# DM1092_uSD.net
KiCad netlist of a schematic drawn in Altium Designer
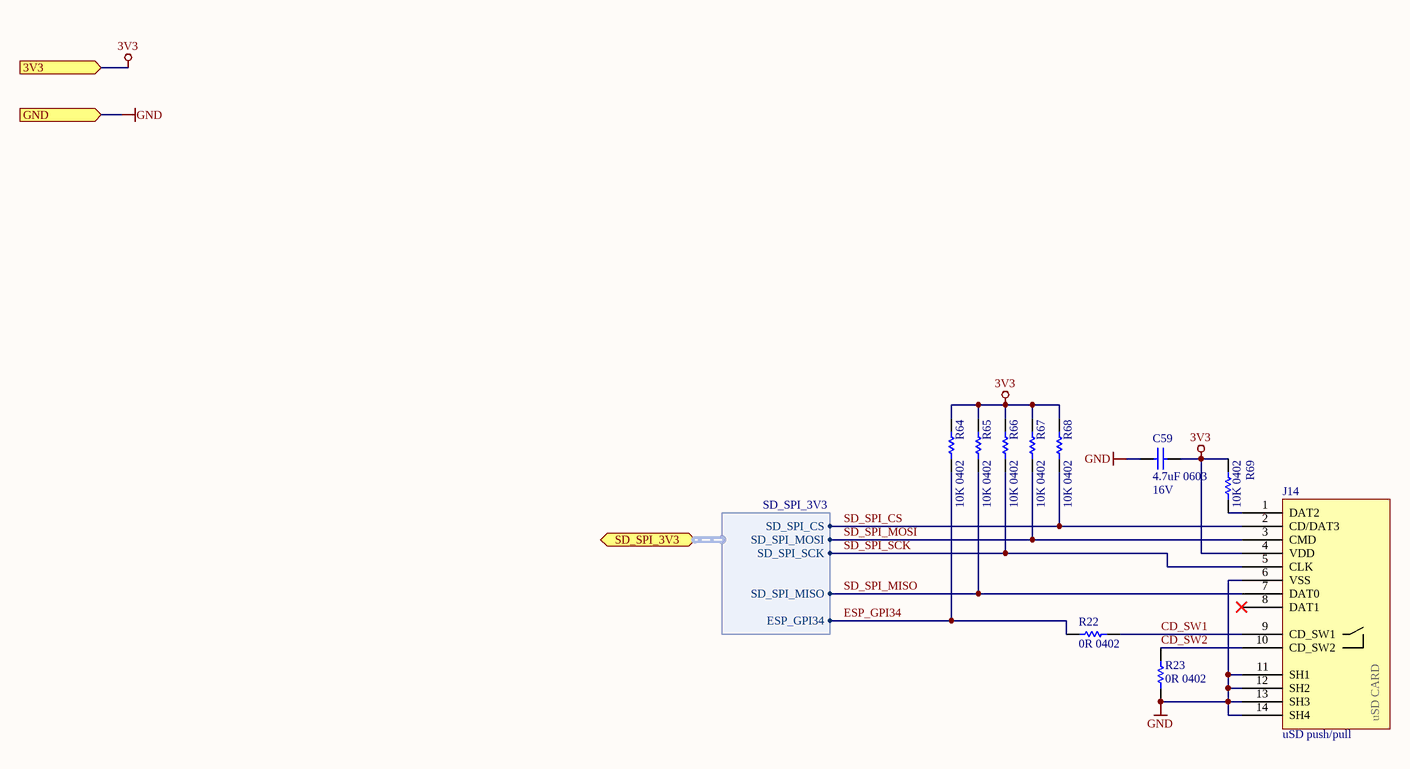
[diagram p0: DM1092_uSD.SchDoc]

(export (version "E")
  (design (tool "Eeschema 10.0.6"))
  (components
    (comp (ref "C59")
      (value "4.7uF 0603")
      (footprint "CAP_Altium_Vault_Generic:CAPC0603(1608)100_N")
      (description "CAP CER 4.7UF 16V X5R 0603 10%")
      (fields (field (name "TOLERANCE") "10%") (field (name "VOLTAGE RATING") "16V"))
      (libsource (lib "LuxonisMaster") (part "GRM188R61C475KAAJD"))
    )
    (comp (ref "J14")
      (value "uSD push/pull")
      (footprint "LuxonisMaster:104031-0811")
      (description "CONN MICRO SD CARD PUSH-PULL R/A")
      (libsource (lib "LuxonisMaster") (part "104031-0811"))
    )
    (comp (ref "R22")
      (value "0R 0402")
      (footprint "RES_Altium_Vault_Generic:RESC0402(1005)_N")
      (description "RES SMD 0 OHM JUMPER 1/16W 0402")
      (fields (field (name "TOLERANCE") "5%"))
      (libsource (lib "LuxonisMaster") (part "CRCW04020000Z0ED"))
    )
    (comp (ref "R23")
      (value "0R 0402")
      (footprint "RES_Altium_Vault_Generic:RESC0402(1005)_N")
      (description "RES SMD 0 OHM JUMPER 1/16W 0402")
      (fields (field (name "TOLERANCE") "5%"))
      (libsource (lib "LuxonisMaster") (part "CRCW04020000Z0ED"))
    )
    (comp (ref "R64")
      (value "10K 0402")
      (footprint "RES_Altium_Vault_Generic:RESC0402(1005)_N")
      (fields (field (name "TOLERANCE") "1%"))
      (libsource (lib "LuxonisMaster") (part "RC0402FR-1310KL"))
    )
    (comp (ref "R65")
      (value "10K 0402")
      (footprint "RES_Altium_Vault_Generic:RESC0402(1005)_N")
      (fields (field (name "TOLERANCE") "1%"))
      (libsource (lib "LuxonisMaster") (part "RC0402FR-1310KL"))
    )
    (comp (ref "R66")
      (value "10K 0402")
      (footprint "RES_Altium_Vault_Generic:RESC0402(1005)_N")
      (fields (field (name "TOLERANCE") "1%"))
      (libsource (lib "LuxonisMaster") (part "RC0402FR-1310KL"))
    )
    (comp (ref "R67")
      (value "10K 0402")
      (footprint "RES_Altium_Vault_Generic:RESC0402(1005)_N")
      (fields (field (name "TOLERANCE") "1%"))
      (libsource (lib "LuxonisMaster") (part "RC0402FR-1310KL"))
    )
    (comp (ref "R68")
      (value "10K 0402")
      (footprint "RES_Altium_Vault_Generic:RESC0402(1005)_N")
      (fields (field (name "TOLERANCE") "1%"))
      (libsource (lib "LuxonisMaster") (part "RC0402FR-1310KL"))
    )
    (comp (ref "R69")
      (value "10K 0402")
      (footprint "RES_Altium_Vault_Generic:RESC0402(1005)_N")
      (fields (field (name "TOLERANCE") "1%"))
      (libsource (lib "LuxonisMaster") (part "RC0402FR-1310KL"))
    )
  )
  (nets
    (net (code "2") (name "/CD_SW1") (class "Default")
      (node (ref "J14") (pin "9") (pinfunction "CD_SW1_9") (pintype "passive"))
      (node (ref "R22") (pin "1") (pinfunction "1_1") (pintype "passive"))
    )
    (net (code "3") (name "/CD_SW2") (class "Default")
      (node (ref "J14") (pin "10") (pinfunction "CD_SW2_10") (pintype "passive"))
      (node (ref "R23") (pin "2") (pinfunction "2_2") (pintype "passive"))
    )
    (net (code "4") (name "/ESP_GPI34") (class "Default")
      (node (ref "R22") (pin "2") (pinfunction "2_2") (pintype "passive"))
      (node (ref "R64") (pin "1") (pinfunction "1_1") (pintype "passive"))
    )
    (net (code "5") (name "/SD_SPI_CS") (class "Default")
      (node (ref "J14") (pin "2") (pinfunction "CD/DAT3_2") (pintype "passive"))
      (node (ref "R68") (pin "1") (pinfunction "1_1") (pintype "passive"))
    )
    (net (code "6") (name "/SD_SPI_MISO") (class "Default")
      (node (ref "J14") (pin "7") (pinfunction "DAT0_7") (pintype "passive"))
      (node (ref "R65") (pin "1") (pinfunction "1_1") (pintype "passive"))
    )
    (net (code "7") (name "/SD_SPI_MOSI") (class "Default")
      (node (ref "J14") (pin "3") (pinfunction "CMD_3") (pintype "passive"))
      (node (ref "R67") (pin "1") (pinfunction "1_1") (pintype "passive"))
    )
    (net (code "8") (name "/SD_SPI_SCK") (class "Default")
      (node (ref "J14") (pin "5") (pinfunction "CLK_5") (pintype "passive"))
      (node (ref "R66") (pin "1") (pinfunction "1_1") (pintype "passive"))
    )
    (net (code "10") (name "3V3") (class "Default")
      (node (ref "C59") (pin "2") (pinfunction "2_2") (pintype "passive"))
      (node (ref "J14") (pin "4") (pinfunction "VDD_4") (pintype "passive"))
      (node (ref "R64") (pin "2") (pinfunction "2_2") (pintype "passive"))
      (node (ref "R65") (pin "2") (pinfunction "2_2") (pintype "passive"))
      (node (ref "R66") (pin "2") (pinfunction "2_2") (pintype "passive"))
      (node (ref "R67") (pin "2") (pinfunction "2_2") (pintype "passive"))
      (node (ref "R68") (pin "2") (pinfunction "2_2") (pintype "passive"))
      (node (ref "R69") (pin "2") (pinfunction "2_2") (pintype "passive"))
    )
    (net (code "11") (name "GND") (class "Default")
      (node (ref "C59") (pin "1") (pinfunction "1_1") (pintype "passive"))
      (node (ref "J14") (pin "11") (pinfunction "SH1_11") (pintype "passive"))
      (node (ref "J14") (pin "12") (pinfunction "SH2_12") (pintype "passive"))
      (node (ref "J14") (pin "13") (pinfunction "SH3_13") (pintype "passive"))
      (node (ref "J14") (pin "14") (pinfunction "SH4_14") (pintype "passive"))
      (node (ref "J14") (pin "6") (pinfunction "VSS_6") (pintype "passive"))
      (node (ref "R23") (pin "1") (pinfunction "1_1") (pintype "passive"))
    )
    (net (code "12") (name "Net-(J14-DAT2)") (class "Default")
      (node (ref "J14") (pin "1") (pinfunction "DAT2_1") (pintype "passive"))
      (node (ref "R69") (pin "1") (pinfunction "1_1") (pintype "passive"))
    )
    (net (code "13") (name "unconnected-(J14-DAT1-Pad8)") (class "Default")
      (node (ref "J14") (pin "8") (pinfunction "DAT1_8") (pintype "passive+no_connect"))
    )
  )
)
